# CAN_Node2pi.net
KiCad netlist of a schematic drawn in EAGLE
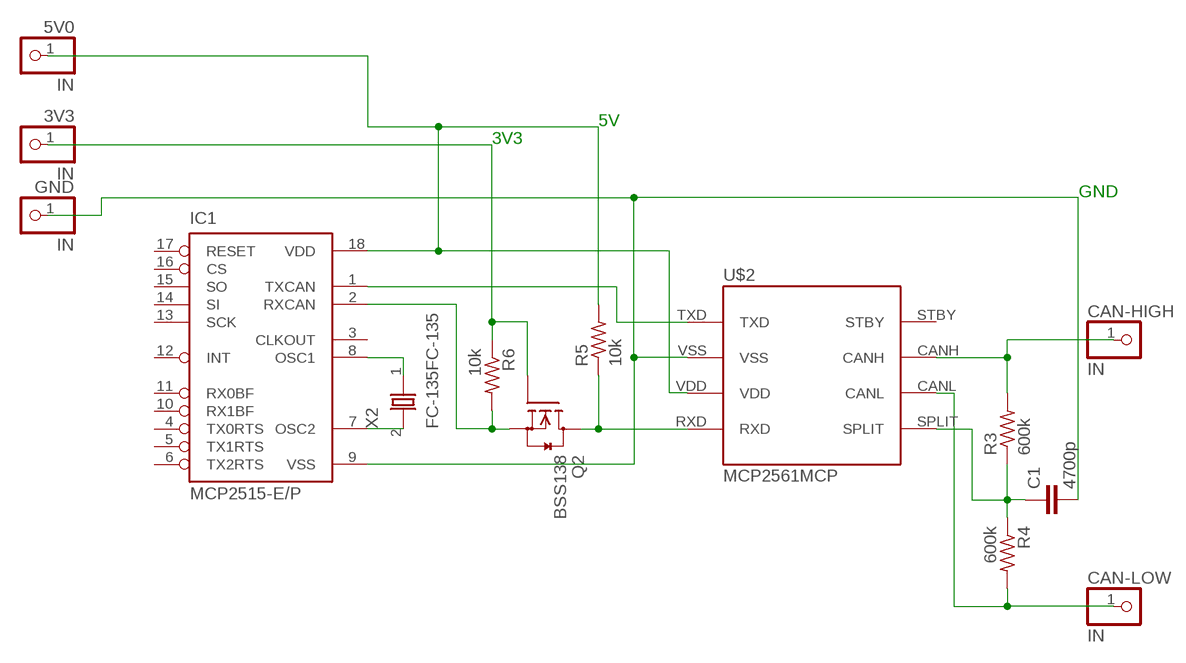
[diagram p0: schematic, sheet 1]

(export (version "E")
  (design (tool "Eeschema 10.0.6"))
  (components
    (comp (ref "3V3")
      (value "IN")
      (footprint "eagle-import:1X01")
      (libsource (lib "eagle-import") (part "PINHD-1X1"))
    )
    (comp (ref "5V0")
      (value "IN")
      (footprint "eagle-import:1X01")
      (libsource (lib "eagle-import") (part "PINHD-1X1"))
    )
    (comp (ref "C1")
      (value "4700p")
      (footprint "eagle-import:C2.5-2")
      (libsource (lib "eagle-import") (part "C2.5/2"))
    )
    (comp (ref "CAN-HIGH")
      (value "IN")
      (footprint "eagle-import:1X01")
      (libsource (lib "eagle-import") (part "PINHD-1X1"))
    )
    (comp (ref "CAN-LOW")
      (value "IN")
      (footprint "eagle-import:1X01")
      (libsource (lib "eagle-import") (part "PINHD-1X1"))
    )
    (comp (ref "GND")
      (value "IN")
      (footprint "eagle-import:1X01")
      (libsource (lib "eagle-import") (part "PINHD-1X1"))
    )
    (comp (ref "IC1")
      (value "MCP2515-E/P")
      (footprint "eagle-import:DIL18")
      (libsource (lib "eagle-import") (part "MCP2515-E/P"))
    )
    (comp (ref "Q2")
      (value "BSS138")
      (footprint "eagle-import:SOT23")
      (libsource (lib "eagle-import") (part "BSS138"))
    )
    (comp (ref "R3")
      (value "600k")
      (footprint "eagle-import:M2309")
      (libsource (lib "eagle-import") (part "R-US_M2309"))
    )
    (comp (ref "R4")
      (value "600k")
      (footprint "eagle-import:M2309")
      (libsource (lib "eagle-import") (part "R-US_M2309"))
    )
    (comp (ref "R5")
      (value "10k")
      (footprint "eagle-import:M2309")
      (libsource (lib "eagle-import") (part "R-US_M2309"))
    )
    (comp (ref "R6")
      (value "10k")
      (footprint "eagle-import:M2309")
      (libsource (lib "eagle-import") (part "R-US_M2309"))
    )
    (comp (ref "U$2")
      (value "MCP2561MCP")
      (footprint "eagle-import:MCP2561_PDIP")
      (libsource (lib "eagle-import") (part "MCP2561MCP"))
    )
    (comp (ref "X2")
      (value "FC-135FC-135")
      (footprint "eagle-import:FC-135")
      (libsource (lib "eagle-import") (part "FC-135FC-135"))
    )
  )
  (nets
    (net (code "1") (name "Net-(C1-Pad1)") (class "Default")
      (node (ref "C1") (pin "1") (pinfunction "1_1") (pintype "passive"))
      (node (ref "R3") (pin "1") (pinfunction "1_1") (pintype "passive"))
      (node (ref "R4") (pin "1") (pinfunction "1_1") (pintype "passive"))
      (node (ref "U$2") (pin "SPLIT") (pinfunction "SPLIT_SPLIT") (pintype "bidirectional"))
    )
    (net (code "2") (name "Net-(CAN-HIGH-Pad1)") (class "Default")
      (node (ref "CAN-HIGH") (pin "1") (pinfunction "1_1") (pintype "passive"))
      (node (ref "R3") (pin "2") (pinfunction "2_2") (pintype "passive"))
      (node (ref "U$2") (pin "CANH") (pinfunction "CANH_CANH") (pintype "bidirectional"))
    )
    (net (code "3") (name "Net-(CAN-LOW-Pad1)") (class "Default")
      (node (ref "CAN-LOW") (pin "1") (pinfunction "1_1") (pintype "passive"))
      (node (ref "R4") (pin "2") (pinfunction "2_2") (pintype "passive"))
      (node (ref "U$2") (pin "CANL") (pinfunction "CANL_CANL") (pintype "bidirectional"))
    )
    (net (code "4") (name "Net-(IC1-OSC1)") (class "Default")
      (node (ref "IC1") (pin "8") (pinfunction "OSC1_8") (pintype "input"))
      (node (ref "X2") (pin "1") (pinfunction "1_1") (pintype "passive"))
    )
    (net (code "5") (name "Net-(IC1-OSC2)") (class "Default")
      (node (ref "IC1") (pin "7") (pinfunction "OSC2_7") (pintype "output"))
      (node (ref "X2") (pin "2") (pinfunction "2_2") (pintype "passive"))
    )
    (net (code "6") (name "Net-(IC1-RXCAN)") (class "Default")
      (node (ref "IC1") (pin "2") (pinfunction "RXCAN_2") (pintype "input"))
      (node (ref "Q2") (pin "2") (pinfunction "S_2") (pintype "passive"))
      (node (ref "R6") (pin "2") (pinfunction "2_2") (pintype "passive"))
    )
    (net (code "7") (name "Net-(IC1-TXCAN)") (class "Default")
      (node (ref "IC1") (pin "1") (pinfunction "TXCAN_1") (pintype "output"))
      (node (ref "U$2") (pin "TXD") (pinfunction "TXD_TXD") (pintype "bidirectional"))
    )
    (net (code "8") (name "Net-(IC1-VDD)") (class "Default")
      (node (ref "5V0") (pin "1") (pinfunction "1_1") (pintype "passive"))
      (node (ref "IC1") (pin "18") (pinfunction "VDD_18") (pintype "power_in"))
      (node (ref "R5") (pin "2") (pinfunction "2_2") (pintype "passive"))
      (node (ref "U$2") (pin "VDD") (pinfunction "VDD_VDD") (pintype "bidirectional"))
    )
    (net (code "9") (name "Net-(IC1-VSS)") (class "Default")
      (node (ref "C1") (pin "2") (pinfunction "2_2") (pintype "passive"))
      (node (ref "GND") (pin "1") (pinfunction "1_1") (pintype "passive"))
      (node (ref "IC1") (pin "9") (pinfunction "VSS_9") (pintype "power_in"))
      (node (ref "U$2") (pin "VSS") (pinfunction "VSS_VSS") (pintype "bidirectional"))
    )
    (net (code "10") (name "Net-(Q2-D)") (class "Default")
      (node (ref "Q2") (pin "3") (pinfunction "D_3") (pintype "passive"))
      (node (ref "R5") (pin "1") (pinfunction "1_1") (pintype "passive"))
      (node (ref "U$2") (pin "RXD") (pinfunction "RXD_RXD") (pintype "bidirectional"))
    )
    (net (code "11") (name "Net-(Q2-G)") (class "Default")
      (node (ref "3V3") (pin "1") (pinfunction "1_1") (pintype "passive"))
      (node (ref "Q2") (pin "1") (pinfunction "G_1") (pintype "passive"))
      (node (ref "R6") (pin "1") (pinfunction "1_1") (pintype "passive"))
    )
    (net (code "12") (name "unconnected-(IC1-CLKOUT-Pad3)") (class "Default")
      (node (ref "IC1") (pin "3") (pinfunction "CLKOUT_3") (pintype "output"))
    )
    (net (code "13") (name "unconnected-(IC1-CS-Pad16)") (class "Default")
      (node (ref "IC1") (pin "16") (pinfunction "CS_16") (pintype "input"))
    )
    (net (code "14") (name "unconnected-(IC1-INT-Pad12)") (class "Default")
      (node (ref "IC1") (pin "12") (pinfunction "INT_12") (pintype "output"))
    )
    (net (code "15") (name "unconnected-(IC1-RESET-Pad17)") (class "Default")
      (node (ref "IC1") (pin "17") (pinfunction "RESET_17") (pintype "input"))
    )
    (net (code "16") (name "unconnected-(IC1-RX0BF-Pad11)") (class "Default")
      (node (ref "IC1") (pin "11") (pinfunction "RX0BF_11") (pintype "output"))
    )
    (net (code "17") (name "unconnected-(IC1-RX1BF-Pad10)") (class "Default")
      (node (ref "IC1") (pin "10") (pinfunction "RX1BF_10") (pintype "output"))
    )
    (net (code "18") (name "unconnected-(IC1-SCK-Pad13)") (class "Default")
      (node (ref "IC1") (pin "13") (pinfunction "SCK_13") (pintype "input"))
    )
    (net (code "19") (name "unconnected-(IC1-SI-Pad14)") (class "Default")
      (node (ref "IC1") (pin "14") (pinfunction "SI_14") (pintype "input"))
    )
    (net (code "20") (name "unconnected-(IC1-SO-Pad15)") (class "Default")
      (node (ref "IC1") (pin "15") (pinfunction "SO_15") (pintype "output"))
    )
    (net (code "21") (name "unconnected-(IC1-TX0RTS-Pad4)") (class "Default")
      (node (ref "IC1") (pin "4") (pinfunction "TX0RTS_4") (pintype "input"))
    )
    (net (code "22") (name "unconnected-(IC1-TX1RTS-Pad5)") (class "Default")
      (node (ref "IC1") (pin "5") (pinfunction "TX1RTS_5") (pintype "input"))
    )
    (net (code "23") (name "unconnected-(IC1-TX2RTS-Pad6)") (class "Default")
      (node (ref "IC1") (pin "6") (pinfunction "TX2RTS_6") (pintype "input"))
    )
    (net (code "24") (name "unconnected-(U$2-PadSTBY)") (class "Default")
      (node (ref "U$2") (pin "STBY") (pinfunction "STBY_STBY") (pintype "bidirectional"))
    )
  )
)
